# Sheet1.net
KiCad netlist of a schematic drawn in Altium Designer
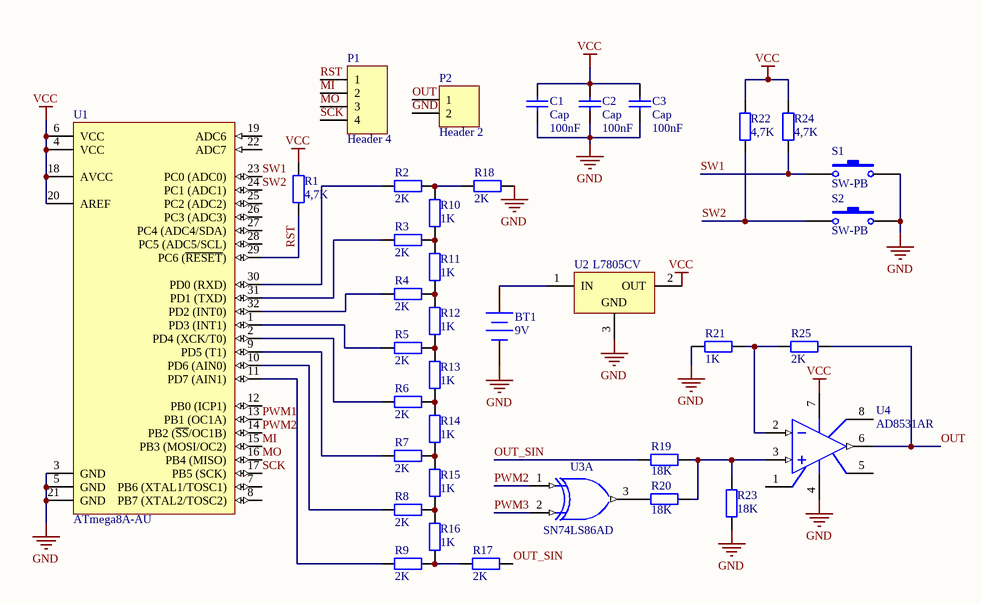
[diagram p0: Sheet1.SchDoc]

(export (version "E")
  (design (tool "Eeschema 10.0.6"))
  (components
    (comp (ref "BT1")
      (value "9V")
      (footprint "BAT-2")
      (description "Multicell Battery")
      (fields (field (name "PUBLISHER") "Altium Limited"))
      (libsource (lib "Miscellaneous Devices") (part "Battery"))
    )
    (comp (ref "C1")
      (value "Cap")
      (footprint "RAD-0.3")
      (description "Capacitor")
      (fields (field (name "ALTIUM_VALUE") "100nF") (field (name "PUBLISHER") "Altium Limited"))
      (libsource (lib "Miscellaneous Devices") (part "Cap"))
    )
    (comp (ref "C2")
      (value "Cap")
      (footprint "RAD-0.3")
      (description "Capacitor")
      (fields (field (name "ALTIUM_VALUE") "100nF") (field (name "PUBLISHER") "Altium Limited"))
      (libsource (lib "Miscellaneous Devices") (part "Cap"))
    )
    (comp (ref "C3")
      (value "Cap")
      (footprint "RAD-0.3")
      (description "Capacitor")
      (fields (field (name "ALTIUM_VALUE") "100nF") (field (name "PUBLISHER") "Altium Limited"))
      (libsource (lib "Miscellaneous Devices") (part "Cap"))
    )
    (comp (ref "P1")
      (value "Header 4")
      (footprint "HDR1X4")
      (description "Header, 4-Pin")
      (fields (field (name "PUBLISHER") "Altium Limited"))
      (libsource (lib "Miscellaneous Connectors") (part "Header 4"))
    )
    (comp (ref "P2")
      (value "Header 2")
      (footprint "HDR1X2")
      (description "Header, 2-Pin")
      (fields (field (name "PUBLISHER") "Altium Limited"))
      (libsource (lib "Miscellaneous Connectors") (part "Header 2"))
    )
    (comp (ref "R1")
      (value "4,7K")
      (footprint "AXIAL-0.4")
      (description "Resistor")
      (fields (field (name "Comment") "Res2") (field (name "PUBLISHER") "Altium Limited"))
      (libsource (lib "") (part "Res2_1"))
    )
    (comp (ref "R2")
      (value "2K")
      (footprint "AXIAL-0.4")
      (description "Resistor")
      (fields (field (name "Comment") "Res2") (field (name "PUBLISHER") "Altium Limited"))
      (libsource (lib "Miscellaneous Devices") (part "Res2"))
    )
    (comp (ref "R3")
      (value "2K")
      (footprint "AXIAL-0.4")
      (description "Resistor")
      (fields (field (name "Comment") "Res2") (field (name "PUBLISHER") "Altium Limited"))
      (libsource (lib "Miscellaneous Devices") (part "Res2"))
    )
    (comp (ref "R4")
      (value "2K")
      (footprint "AXIAL-0.4")
      (description "Resistor")
      (fields (field (name "Comment") "Res2") (field (name "PUBLISHER") "Altium Limited"))
      (libsource (lib "Miscellaneous Devices") (part "Res2"))
    )
    (comp (ref "R5")
      (value "2K")
      (footprint "AXIAL-0.4")
      (description "Resistor")
      (fields (field (name "Comment") "Res2") (field (name "PUBLISHER") "Altium Limited"))
      (libsource (lib "Miscellaneous Devices") (part "Res2"))
    )
    (comp (ref "R6")
      (value "2K")
      (footprint "AXIAL-0.4")
      (description "Resistor")
      (fields (field (name "Comment") "Res2") (field (name "PUBLISHER") "Altium Limited"))
      (libsource (lib "Miscellaneous Devices") (part "Res2"))
    )
    (comp (ref "R7")
      (value "2K")
      (footprint "AXIAL-0.4")
      (description "Resistor")
      (fields (field (name "Comment") "Res2") (field (name "PUBLISHER") "Altium Limited"))
      (libsource (lib "Miscellaneous Devices") (part "Res2"))
    )
    (comp (ref "R8")
      (value "2K")
      (footprint "AXIAL-0.4")
      (description "Resistor")
      (fields (field (name "Comment") "Res2") (field (name "PUBLISHER") "Altium Limited"))
      (libsource (lib "Miscellaneous Devices") (part "Res2"))
    )
    (comp (ref "R9")
      (value "2K")
      (footprint "AXIAL-0.4")
      (description "Resistor")
      (fields (field (name "Comment") "Res2") (field (name "PUBLISHER") "Altium Limited"))
      (libsource (lib "Miscellaneous Devices") (part "Res2"))
    )
    (comp (ref "R10")
      (value "1K")
      (footprint "AXIAL-0.4")
      (description "Resistor")
      (fields (field (name "Comment") "Res2") (field (name "PUBLISHER") "Altium Limited"))
      (libsource (lib "") (part "Res2_1"))
    )
    (comp (ref "R11")
      (value "1K")
      (footprint "AXIAL-0.4")
      (description "Resistor")
      (fields (field (name "Comment") "Res2") (field (name "PUBLISHER") "Altium Limited"))
      (libsource (lib "") (part "Res2_1"))
    )
    (comp (ref "R12")
      (value "1K")
      (footprint "AXIAL-0.4")
      (description "Resistor")
      (fields (field (name "Comment") "Res2") (field (name "PUBLISHER") "Altium Limited"))
      (libsource (lib "") (part "Res2_1"))
    )
    (comp (ref "R13")
      (value "1K")
      (footprint "AXIAL-0.4")
      (description "Resistor")
      (fields (field (name "Comment") "Res2") (field (name "PUBLISHER") "Altium Limited"))
      (libsource (lib "") (part "Res2_1"))
    )
    (comp (ref "R14")
      (value "1K")
      (footprint "AXIAL-0.4")
      (description "Resistor")
      (fields (field (name "Comment") "Res2") (field (name "PUBLISHER") "Altium Limited"))
      (libsource (lib "") (part "Res2_1"))
    )
    (comp (ref "R15")
      (value "1K")
      (footprint "AXIAL-0.4")
      (description "Resistor")
      (fields (field (name "Comment") "Res2") (field (name "PUBLISHER") "Altium Limited"))
      (libsource (lib "") (part "Res2_1"))
    )
    (comp (ref "R16")
      (value "1K")
      (footprint "AXIAL-0.4")
      (description "Resistor")
      (fields (field (name "Comment") "Res2") (field (name "PUBLISHER") "Altium Limited"))
      (libsource (lib "") (part "Res2_1"))
    )
    (comp (ref "R17")
      (value "2K")
      (footprint "AXIAL-0.4")
      (description "Resistor")
      (fields (field (name "Comment") "Res2") (field (name "PUBLISHER") "Altium Limited"))
      (libsource (lib "Miscellaneous Devices") (part "Res2"))
    )
    (comp (ref "R18")
      (value "2K")
      (footprint "AXIAL-0.4")
      (description "Resistor")
      (fields (field (name "Comment") "Res2") (field (name "PUBLISHER") "Altium Limited"))
      (libsource (lib "Miscellaneous Devices") (part "Res2"))
    )
    (comp (ref "R19")
      (value "18K")
      (footprint "AXIAL-0.4")
      (description "Resistor")
      (fields (field (name "Comment") "Res2") (field (name "PUBLISHER") "Altium Limited"))
      (libsource (lib "Miscellaneous Devices") (part "Res2"))
    )
    (comp (ref "R20")
      (value "18K")
      (footprint "AXIAL-0.4")
      (description "Resistor")
      (fields (field (name "Comment") "Res2") (field (name "PUBLISHER") "Altium Limited"))
      (libsource (lib "Miscellaneous Devices") (part "Res2"))
    )
    (comp (ref "R21")
      (value "1K")
      (footprint "AXIAL-0.4")
      (description "Resistor")
      (fields (field (name "Comment") "Res2") (field (name "PUBLISHER") "Altium Limited"))
      (libsource (lib "Miscellaneous Devices") (part "Res2"))
    )
    (comp (ref "R22")
      (value "4,7K")
      (footprint "AXIAL-0.4")
      (description "Resistor")
      (fields (field (name "Comment") "Res2") (field (name "PUBLISHER") "Altium Limited"))
      (libsource (lib "") (part "Res2_1"))
    )
    (comp (ref "R23")
      (value "18K")
      (footprint "AXIAL-0.4")
      (description "Resistor")
      (fields (field (name "Comment") "Res2") (field (name "PUBLISHER") "Altium Limited"))
      (libsource (lib "") (part "Res2_2"))
    )
    (comp (ref "R24")
      (value "4,7K")
      (footprint "AXIAL-0.4")
      (description "Resistor")
      (fields (field (name "Comment") "Res2") (field (name "PUBLISHER") "Altium Limited"))
      (libsource (lib "") (part "Res2_1"))
    )
    (comp (ref "R25")
      (value "2K")
      (footprint "AXIAL-0.4")
      (description "Resistor")
      (fields (field (name "Comment") "Res2") (field (name "PUBLISHER") "Altium Limited"))
      (libsource (lib "Miscellaneous Devices") (part "Res2"))
    )
    (comp (ref "S1")
      (value "SW-PB")
      (footprint "SPST-2")
      (description "Switch")
      (fields (field (name "PUBLISHER") "Altium Limited"))
      (libsource (lib "Miscellaneous Devices") (part "SW-PB"))
    )
    (comp (ref "S2")
      (value "SW-PB")
      (footprint "SPST-2")
      (description "Switch")
      (fields (field (name "PUBLISHER") "Altium Limited"))
      (libsource (lib "Miscellaneous Devices") (part "SW-PB"))
    )
    (comp (ref "U1")
      (value "ATmega8A-AU")
      (footprint "32A_N")
      (fields (field (name "PUBLISHER") "Altium Limited"))
      (libsource (lib "Atmel Microcontroller 8-Bit megaAVR") (part "ATmega8A-AU"))
    )
    (comp (ref "U2")
      (value "L7805CV")
      (footprint "TO220ABN")
      (description "Positive Voltage Regulator")
      (fields (field (name "PUBLISHER") "Altium Limited"))
      (libsource (lib "ST Power Mgt Voltage Regulator") (part "L7805CV"))
    )
    (comp (ref "U3")
      (value "SN74LS86AD")
      (footprint "D014_N")
      (description "Quadruple 2-Input Exclusive-OR Gate")
      (fields (field (name "PUBLISHER") "Altium Limited"))
      (libsource (lib "TI Logic Gate 2") (part "SN74LS86AD"))
    )
    (comp (ref "U4")
      (value "AD8531AR")
      (footprint "SO-8_N")
      (description "Low Cost, 250 mA Output Single-Supply Amplifier")
      (fields (field (name "PUBLISHER") "Altium Limited"))
      (libsource (lib "AD Operational Amplifier") (part "AD8531AR"))
    )
  )
  (nets
    (net (code "1") (name "/MI") (class "Default")
      (node (ref "P1") (pin "2") (pinfunction "2_2") (pintype "passive"))
      (node (ref "U1") (pin "15") (pinfunction "PB3_(MOSI/OC2)_15") (pintype "bidirectional"))
    )
    (net (code "2") (name "/MO") (class "Default")
      (node (ref "P1") (pin "3") (pinfunction "3_3") (pintype "passive"))
      (node (ref "U1") (pin "16") (pinfunction "PB4_(MISO)_16") (pintype "bidirectional"))
    )
    (net (code "3") (name "/OUT") (class "Default")
      (node (ref "P2") (pin "1") (pinfunction "1_1") (pintype "passive"))
      (node (ref "R25") (pin "2") (pinfunction "2_2") (pintype "passive"))
      (node (ref "U4") (pin "6") (pinfunction "OUT_6") (pintype "output"))
    )
    (net (code "4") (name "/OUT_SIN") (class "Default")
      (node (ref "R17") (pin "2") (pinfunction "2_2") (pintype "passive"))
      (node (ref "R19") (pin "1") (pinfunction "1_1") (pintype "passive"))
    )
    (net (code "5") (name "/PWM1") (class "Default")
      (node (ref "U1") (pin "13") (pinfunction "PB1_(OC1A)_13") (pintype "bidirectional"))
    )
    (net (code "6") (name "/PWM2") (class "Default")
      (node (ref "U1") (pin "14") (pinfunction "PB2_(~{SS}/OC1B)_14") (pintype "bidirectional"))
      (node (ref "U3") (pin "1") (pinfunction "A_1") (pintype "input"))
    )
    (net (code "7") (name "/PWM3") (class "Default")
      (node (ref "U3") (pin "2") (pinfunction "B_2") (pintype "input"))
    )
    (net (code "8") (name "/RST") (class "Default")
      (node (ref "P1") (pin "1") (pinfunction "1_1") (pintype "passive"))
      (node (ref "R1") (pin "1") (pinfunction "1_1") (pintype "passive"))
      (node (ref "U1") (pin "29") (pinfunction "PC6_(~{RESET})_29") (pintype "bidirectional"))
    )
    (net (code "9") (name "/SCK") (class "Default")
      (node (ref "P1") (pin "4") (pinfunction "4_4") (pintype "passive"))
      (node (ref "U1") (pin "17") (pinfunction "PB5_(SCK)_17") (pintype "bidirectional"))
    )
    (net (code "10") (name "/SW1") (class "Default")
      (node (ref "R24") (pin "1") (pinfunction "1_1") (pintype "passive"))
      (node (ref "S1") (pin "1") (pinfunction "1_1") (pintype "passive"))
      (node (ref "U1") (pin "23") (pinfunction "PC0_(ADC0)_23") (pintype "bidirectional"))
    )
    (net (code "11") (name "/SW2") (class "Default")
      (node (ref "R22") (pin "1") (pinfunction "1_1") (pintype "passive"))
      (node (ref "S2") (pin "1") (pinfunction "1_1") (pintype "passive"))
      (node (ref "U1") (pin "24") (pinfunction "PC1_(ADC1)_24") (pintype "bidirectional"))
    )
    (net (code "12") (name "GND") (class "Default")
      (node (ref "BT1") (pin "2") (pinfunction "-_2") (pintype "passive"))
      (node (ref "C1") (pin "1") (pinfunction "1_1") (pintype "passive"))
      (node (ref "C2") (pin "1") (pinfunction "1_1") (pintype "passive"))
      (node (ref "C3") (pin "1") (pinfunction "1_1") (pintype "passive"))
      (node (ref "P2") (pin "2") (pinfunction "2_2") (pintype "passive"))
      (node (ref "R18") (pin "2") (pinfunction "2_2") (pintype "passive"))
      (node (ref "R21") (pin "1") (pinfunction "1_1") (pintype "passive"))
      (node (ref "R23") (pin "2") (pinfunction "2_2") (pintype "passive"))
      (node (ref "S1") (pin "2") (pinfunction "2_2") (pintype "passive"))
      (node (ref "S2") (pin "2") (pinfunction "2_2") (pintype "passive"))
      (node (ref "U1") (pin "21") (pinfunction "GND_21") (pintype "power_in"))
      (node (ref "U1") (pin "3") (pinfunction "GND_3") (pintype "power_in"))
      (node (ref "U1") (pin "5") (pinfunction "GND_5") (pintype "power_in"))
      (node (ref "U2") (pin "3") (pinfunction "GND_3") (pintype "power_in"))
      (node (ref "U3") (pin "7") (pinfunction "GND_7") (pintype "power_in"))
      (node (ref "U4") (pin "4") (pinfunction "V-_4") (pintype "power_in"))
    )
    (net (code "13") (name "Net-(BT1-+)") (class "Default")
      (node (ref "BT1") (pin "1") (pinfunction "+_1") (pintype "passive"))
      (node (ref "U2") (pin "1") (pinfunction "IN_1") (pintype "power_in"))
    )
    (net (code "14") (name "Net-(R10-Pad1)") (class "Default")
      (node (ref "R10") (pin "1") (pinfunction "1_1") (pintype "passive"))
      (node (ref "R11") (pin "2") (pinfunction "2_2") (pintype "passive"))
      (node (ref "R3") (pin "2") (pinfunction "2_2") (pintype "passive"))
    )
    (net (code "15") (name "Net-(R10-Pad2)") (class "Default")
      (node (ref "R10") (pin "2") (pinfunction "2_2") (pintype "passive"))
      (node (ref "R18") (pin "1") (pinfunction "1_1") (pintype "passive"))
      (node (ref "R2") (pin "2") (pinfunction "2_2") (pintype "passive"))
    )
    (net (code "16") (name "Net-(R11-Pad1)") (class "Default")
      (node (ref "R11") (pin "1") (pinfunction "1_1") (pintype "passive"))
      (node (ref "R12") (pin "2") (pinfunction "2_2") (pintype "passive"))
      (node (ref "R4") (pin "2") (pinfunction "2_2") (pintype "passive"))
    )
    (net (code "17") (name "Net-(R12-Pad1)") (class "Default")
      (node (ref "R12") (pin "1") (pinfunction "1_1") (pintype "passive"))
      (node (ref "R13") (pin "2") (pinfunction "2_2") (pintype "passive"))
      (node (ref "R5") (pin "2") (pinfunction "2_2") (pintype "passive"))
    )
    (net (code "18") (name "Net-(R13-Pad1)") (class "Default")
      (node (ref "R13") (pin "1") (pinfunction "1_1") (pintype "passive"))
      (node (ref "R14") (pin "2") (pinfunction "2_2") (pintype "passive"))
      (node (ref "R6") (pin "2") (pinfunction "2_2") (pintype "passive"))
    )
    (net (code "19") (name "Net-(R14-Pad1)") (class "Default")
      (node (ref "R14") (pin "1") (pinfunction "1_1") (pintype "passive"))
      (node (ref "R15") (pin "2") (pinfunction "2_2") (pintype "passive"))
      (node (ref "R7") (pin "2") (pinfunction "2_2") (pintype "passive"))
    )
    (net (code "20") (name "Net-(R15-Pad1)") (class "Default")
      (node (ref "R15") (pin "1") (pinfunction "1_1") (pintype "passive"))
      (node (ref "R16") (pin "2") (pinfunction "2_2") (pintype "passive"))
      (node (ref "R8") (pin "2") (pinfunction "2_2") (pintype "passive"))
    )
    (net (code "21") (name "Net-(R16-Pad1)") (class "Default")
      (node (ref "R16") (pin "1") (pinfunction "1_1") (pintype "passive"))
      (node (ref "R17") (pin "1") (pinfunction "1_1") (pintype "passive"))
      (node (ref "R9") (pin "2") (pinfunction "2_2") (pintype "passive"))
    )
    (net (code "22") (name "Net-(U1-PD0_(RXD))") (class "Default")
      (node (ref "R2") (pin "1") (pinfunction "1_1") (pintype "passive"))
      (node (ref "U1") (pin "30") (pinfunction "PD0_(RXD)_30") (pintype "bidirectional"))
    )
    (net (code "23") (name "Net-(U1-PD1_(TXD))") (class "Default")
      (node (ref "R3") (pin "1") (pinfunction "1_1") (pintype "passive"))
      (node (ref "U1") (pin "31") (pinfunction "PD1_(TXD)_31") (pintype "bidirectional"))
    )
    (net (code "24") (name "Net-(U1-PD2_(INT0))") (class "Default")
      (node (ref "R4") (pin "1") (pinfunction "1_1") (pintype "passive"))
      (node (ref "U1") (pin "32") (pinfunction "PD2_(INT0)_32") (pintype "bidirectional"))
    )
    (net (code "25") (name "Net-(U1-PD3_(INT1))") (class "Default")
      (node (ref "R5") (pin "1") (pinfunction "1_1") (pintype "passive"))
      (node (ref "U1") (pin "1") (pinfunction "PD3_(INT1)_1") (pintype "bidirectional"))
    )
    (net (code "26") (name "Net-(U1-PD4_(XCK{slash}T0))") (class "Default")
      (node (ref "R6") (pin "1") (pinfunction "1_1") (pintype "passive"))
      (node (ref "U1") (pin "2") (pinfunction "PD4_(XCK/T0)_2") (pintype "bidirectional"))
    )
    (net (code "27") (name "Net-(U1-PD5_(T1))") (class "Default")
      (node (ref "R7") (pin "1") (pinfunction "1_1") (pintype "passive"))
      (node (ref "U1") (pin "9") (pinfunction "PD5_(T1)_9") (pintype "bidirectional"))
    )
    (net (code "28") (name "Net-(U1-PD6_(AIN0))") (class "Default")
      (node (ref "R8") (pin "1") (pinfunction "1_1") (pintype "passive"))
      (node (ref "U1") (pin "10") (pinfunction "PD6_(AIN0)_10") (pintype "bidirectional"))
    )
    (net (code "29") (name "Net-(U1-PD7_(AIN1))") (class "Default")
      (node (ref "R9") (pin "1") (pinfunction "1_1") (pintype "passive"))
      (node (ref "U1") (pin "11") (pinfunction "PD7_(AIN1)_11") (pintype "bidirectional"))
    )
    (net (code "30") (name "Net-(U3A-Y)") (class "Default")
      (node (ref "R20") (pin "1") (pinfunction "1_1") (pintype "passive"))
      (node (ref "U3") (pin "3") (pinfunction "Y_3") (pintype "output"))
    )
    (net (code "31") (name "Net-(U4-IN+)") (class "Default")
      (node (ref "R19") (pin "2") (pinfunction "2_2") (pintype "passive"))
      (node (ref "R20") (pin "2") (pinfunction "2_2") (pintype "passive"))
      (node (ref "R23") (pin "1") (pinfunction "1_1") (pintype "passive"))
      (node (ref "U4") (pin "3") (pinfunction "IN+_3") (pintype "input"))
    )
    (net (code "32") (name "Net-(U4-IN-)") (class "Default")
      (node (ref "R21") (pin "2") (pinfunction "2_2") (pintype "passive"))
      (node (ref "R25") (pin "1") (pinfunction "1_1") (pintype "passive"))
      (node (ref "U4") (pin "2") (pinfunction "IN-_2") (pintype "input"))
    )
    (net (code "33") (name "VCC") (class "Default")
      (node (ref "C1") (pin "2") (pinfunction "2_2") (pintype "passive"))
      (node (ref "C2") (pin "2") (pinfunction "2_2") (pintype "passive"))
      (node (ref "C3") (pin "2") (pinfunction "2_2") (pintype "passive"))
      (node (ref "R1") (pin "2") (pinfunction "2_2") (pintype "passive"))
      (node (ref "R22") (pin "2") (pinfunction "2_2") (pintype "passive"))
      (node (ref "R24") (pin "2") (pinfunction "2_2") (pintype "passive"))
      (node (ref "U1") (pin "18") (pinfunction "AVCC_18") (pintype "power_in"))
      (node (ref "U1") (pin "20") (pinfunction "AREF_20") (pintype "power_in"))
      (node (ref "U1") (pin "4") (pinfunction "VCC_4") (pintype "power_in"))
      (node (ref "U1") (pin "6") (pinfunction "VCC_6") (pintype "power_in"))
      (node (ref "U2") (pin "2") (pinfunction "OUT_2") (pintype "power_in"))
      (node (ref "U3") (pin "14") (pinfunction "VCC_14") (pintype "power_in"))
      (node (ref "U4") (pin "7") (pinfunction "V+_7") (pintype "power_in"))
    )
    (net (code "34") (name "unconnected-(U1-ADC6-Pad19)") (class "Default")
      (node (ref "U1") (pin "19") (pinfunction "ADC6_19") (pintype "input"))
    )
    (net (code "35") (name "unconnected-(U1-ADC7-Pad22)") (class "Default")
      (node (ref "U1") (pin "22") (pinfunction "ADC7_22") (pintype "input"))
    )
    (net (code "36") (name "unconnected-(U1-PB0_(ICP1)-Pad12)") (class "Default")
      (node (ref "U1") (pin "12") (pinfunction "PB0_(ICP1)_12") (pintype "bidirectional"))
    )
    (net (code "37") (name "unconnected-(U1-PB6_(XTAL1{slash}TOSC1)-Pad7)") (class "Default")
      (node (ref "U1") (pin "7") (pinfunction "PB6_(XTAL1/TOSC1)_7") (pintype "bidirectional"))
    )
    (net (code "38") (name "unconnected-(U1-PB7_(XTAL2{slash}TOSC2)-Pad8)") (class "Default")
      (node (ref "U1") (pin "8") (pinfunction "PB7_(XTAL2/TOSC2)_8") (pintype "bidirectional"))
    )
    (net (code "39") (name "unconnected-(U1-PC2_(ADC2)-Pad25)") (class "Default")
      (node (ref "U1") (pin "25") (pinfunction "PC2_(ADC2)_25") (pintype "bidirectional"))
    )
    (net (code "40") (name "unconnected-(U1-PC3_(ADC3)-Pad26)") (class "Default")
      (node (ref "U1") (pin "26") (pinfunction "PC3_(ADC3)_26") (pintype "bidirectional"))
    )
    (net (code "41") (name "unconnected-(U1-PC4_(ADC4{slash}SDA)-Pad27)") (class "Default")
      (node (ref "U1") (pin "27") (pinfunction "PC4_(ADC4/SDA)_27") (pintype "bidirectional"))
    )
    (net (code "42") (name "unconnected-(U1-PC5_(ADC5{slash}SCL)-Pad28)") (class "Default")
      (node (ref "U1") (pin "28") (pinfunction "PC5_(ADC5/SCL)_28") (pintype "bidirectional"))
    )
    (net (code "43") (name "unconnected-(U4-NC-Pad8)") (class "Default")
      (node (ref "U4") (pin "8") (pinfunction "NC_8") (pintype "passive"))
    )
    (net (code "44") (name "unconnected-(U4-OS_NULL-Pad1)") (class "Default")
      (node (ref "U4") (pin "1") (pinfunction "OS_NULL_1") (pintype "passive"))
    )
    (net (code "45") (name "unconnected-(U4-OS_NULL-Pad5)") (class "Default")
      (node (ref "U4") (pin "5") (pinfunction "OS_NULL_5") (pintype "passive"))
    )
  )
)
